# hello_speaker_45.net
KiCad netlist of a schematic drawn in EAGLE
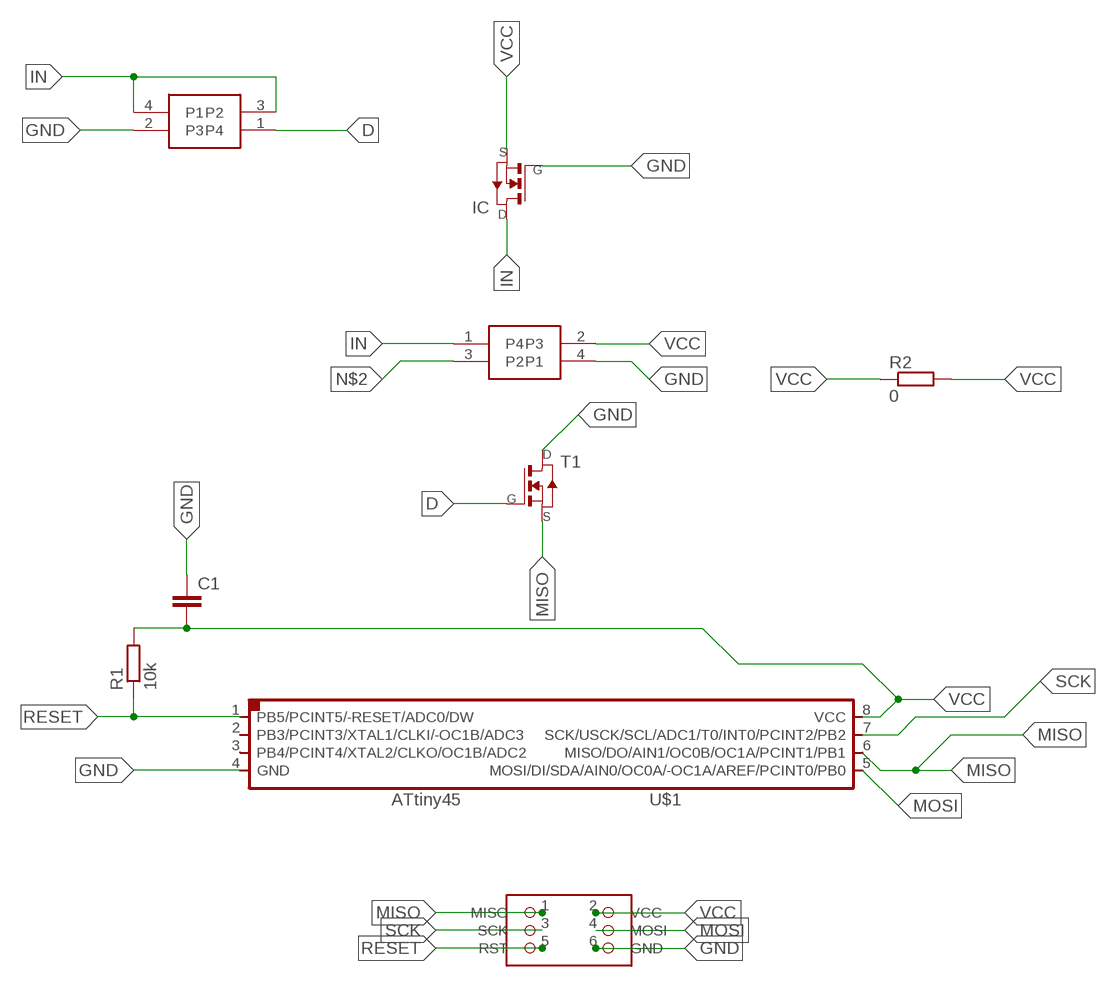
[diagram p0: schematic, sheet 1]

(export (version "E")
  (design (tool "Eeschema 10.0.6"))
  (components
    (comp (ref "C1") (value "C") (footprint "eagle-import:C0805") (libsource (lib "eagle-import") (part "C")))
    (comp (ref "IC")
      (value "NMOSFETSOT23")
      (footprint "eagle-import:SOT-23")
      (libsource (lib "eagle-import") (part "NMOSFETSOT23"))
    )
    (comp (ref "R1")
      (value "10k")
      (footprint "eagle-import:R0805")
      (libsource (lib "eagle-import") (part "R"))
    )
    (comp (ref "R2") (value "0") (footprint "eagle-import:R0805") (libsource (lib "eagle-import") (part "R")))
    (comp (ref "T1")
      (value "NMOSFETSOT23")
      (footprint "eagle-import:SOT-23")
      (libsource (lib "eagle-import") (part "NMOSFETSOT23"))
    )
    (comp (ref "U$1")
      (value "ATTINY45SI")
      (footprint "eagle-import:SOIC8")
      (libsource (lib "eagle-import") (part "ATTINY45SI"))
    )
    (comp (ref "U$2")
      (value "AVRISPSMD")
      (footprint "eagle-import:2X03SMD")
      (libsource (lib "eagle-import") (part "AVRISPSMD"))
    )
    (comp (ref "U$3")
      (value "4PIN-SMD-CONNECTOR")
      (footprint "eagle-import:2X02SMD")
      (libsource (lib "eagle-import") (part "4PIN-SMD-CONNECTOR"))
    )
    (comp (ref "U$4")
      (value "4PIN-SMD-CONNECTOR")
      (footprint "eagle-import:2X02SMD")
      (fields (field (name "SPICEPREFIX") "E"))
      (libsource (lib "eagle-import") (part "4PIN-SMD-CONNECTOR"))
    )
  )
  (nets
    (net (code "1") (name "D") (class "Default")
      (node (ref "T1") (pin "3") (pinfunction "G_3") (pintype "passive"))
      (node (ref "U$3") (pin "1") (pinfunction "P4_1") (pintype "bidirectional"))
    )
    (net (code "2") (name "GND") (class "Default")
      (node (ref "C1") (pin "1") (pinfunction "1_1") (pintype "passive"))
      (node (ref "IC") (pin "3") (pinfunction "G_3") (pintype "passive"))
      (node (ref "T1") (pin "1") (pinfunction "D_1") (pintype "passive"))
      (node (ref "U$1") (pin "4") (pinfunction "GND_4") (pintype "bidirectional"))
      (node (ref "U$2") (pin "6") (pinfunction "GND_6") (pintype "passive"))
      (node (ref "U$3") (pin "2") (pinfunction "P3_2") (pintype "bidirectional"))
      (node (ref "U$4") (pin "4") (pinfunction "P1_4") (pintype "bidirectional"))
    )
    (net (code "3") (name "IN") (class "Default")
      (node (ref "IC") (pin "1") (pinfunction "D_1") (pintype "passive"))
      (node (ref "U$3") (pin "3") (pinfunction "P2_3") (pintype "bidirectional"))
      (node (ref "U$3") (pin "4") (pinfunction "P1_4") (pintype "bidirectional"))
      (node (ref "U$4") (pin "1") (pinfunction "P4_1") (pintype "bidirectional"))
    )
    (net (code "4") (name "MISO") (class "Default")
      (node (ref "T1") (pin "2") (pinfunction "S_2") (pintype "passive"))
      (node (ref "U$1") (pin "6") (pinfunction "MISO/DO/AIN1/OC0B/OC1A/PCINT1/PB1_6") (pintype "bidirectional"))
      (node (ref "U$2") (pin "1") (pinfunction "MISO_1") (pintype "passive"))
    )
    (net (code "5") (name "MOSI") (class "Default")
      (node (ref "U$1") (pin "5") (pinfunction "MOSI/DI/SDA/AIN0/OC0A/-OC1A/AREF/PCINT0/PB0_5") (pintype "bidirectional"))
      (node (ref "U$2") (pin "4") (pinfunction "MOSI_4") (pintype "passive"))
    )
    (net (code "6") (name "N$2") (class "Default")
      (node (ref "U$4") (pin "3") (pinfunction "P2_3") (pintype "bidirectional"))
    )
    (net (code "7") (name "RESET") (class "Default")
      (node (ref "R1") (pin "1") (pinfunction "1_1") (pintype "passive"))
      (node (ref "U$1") (pin "1") (pinfunction "PB5/PCINT5/-RESET/ADC0/DW_1") (pintype "bidirectional"))
      (node (ref "U$2") (pin "5") (pinfunction "RST_5") (pintype "passive"))
    )
    (net (code "8") (name "SCK") (class "Default")
      (node (ref "U$1") (pin "7") (pinfunction "SCK/USCK/SCL/ADC1/T0/INT0/PCINT2/PB2_7") (pintype "bidirectional"))
      (node (ref "U$2") (pin "3") (pinfunction "SCK_3") (pintype "passive"))
    )
    (net (code "9") (name "VCC") (class "Default")
      (node (ref "C1") (pin "2") (pinfunction "2_2") (pintype "passive"))
      (node (ref "IC") (pin "2") (pinfunction "S_2") (pintype "passive"))
      (node (ref "R1") (pin "2") (pinfunction "2_2") (pintype "passive"))
      (node (ref "R2") (pin "1") (pinfunction "1_1") (pintype "passive"))
      (node (ref "R2") (pin "2") (pinfunction "2_2") (pintype "passive"))
      (node (ref "U$1") (pin "8") (pinfunction "VCC_8") (pintype "bidirectional"))
      (node (ref "U$2") (pin "2") (pinfunction "VCC_2") (pintype "passive"))
      (node (ref "U$4") (pin "2") (pinfunction "P3_2") (pintype "bidirectional"))
    )
    (net (code "10") (name "unconnected-(U$1-PB3{slash}PCINT3{slash}XTAL1{slash}CLKI{slash}-OC1B{slash}ADC3-Pad2)") (class "Default")
      (node (ref "U$1") (pin "2") (pinfunction "PB3/PCINT3/XTAL1/CLKI/-OC1B/ADC3_2") (pintype "bidirectional"))
    )
    (net (code "11") (name "unconnected-(U$1-PB4{slash}PCINT4{slash}XTAL2{slash}CLKO{slash}OC1B{slash}ADC2-Pad3)") (class "Default")
      (node (ref "U$1") (pin "3") (pinfunction "PB4/PCINT4/XTAL2/CLKO/OC1B/ADC2_3") (pintype "bidirectional"))
    )
  )
)
